# JOYPAD.net
KiCad netlist of a schematic drawn in EAGLE
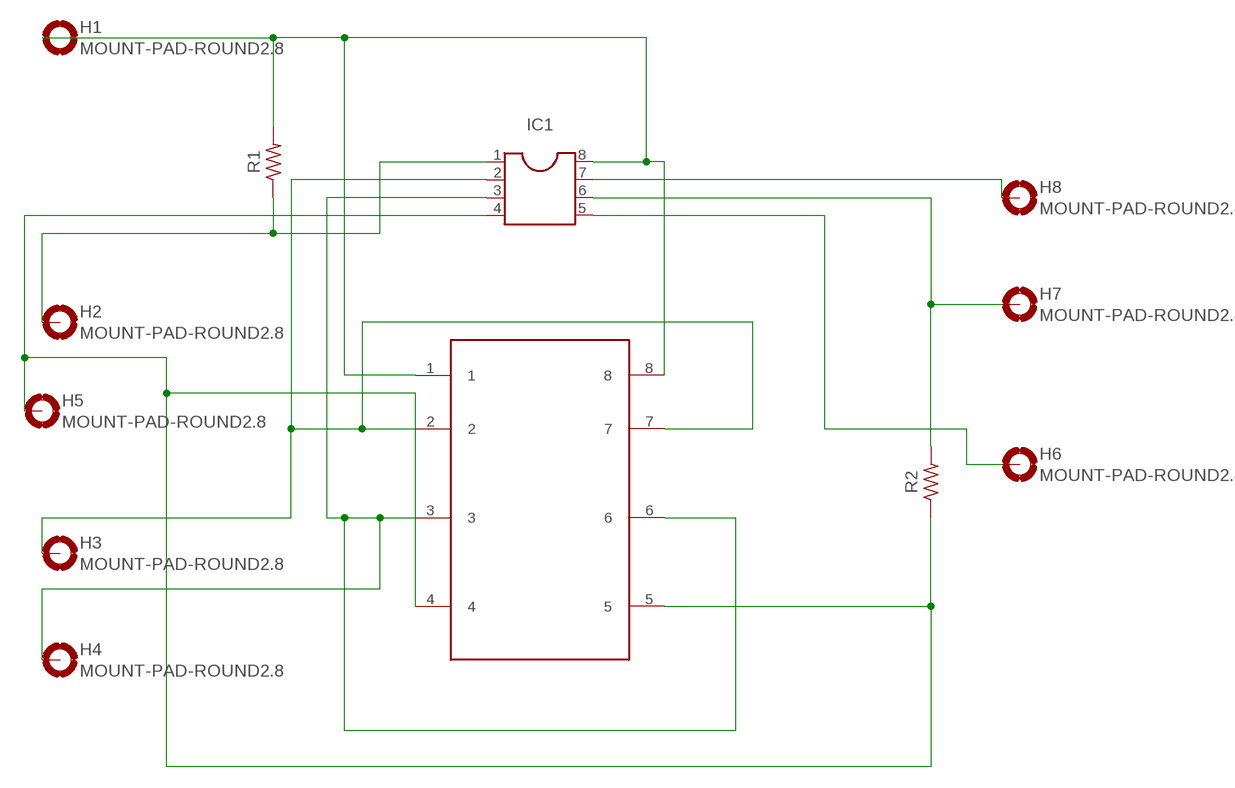
[diagram p0: schematic, sheet 1]

(export (version "E")
  (design (tool "Eeschema 10.0.6"))
  (components
    (comp (ref "H1")
      (value "MOUNT-PAD-ROUND2.8")
      (footprint "eagle-import:2,8-PAD")
      (libsource (lib "eagle-import") (part "MOUNT-PAD-ROUND2.8"))
    )
    (comp (ref "H2")
      (value "MOUNT-PAD-ROUND2.8")
      (footprint "eagle-import:2,8-PAD")
      (libsource (lib "eagle-import") (part "MOUNT-PAD-ROUND2.8"))
    )
    (comp (ref "H3")
      (value "MOUNT-PAD-ROUND2.8")
      (footprint "eagle-import:2,8-PAD")
      (libsource (lib "eagle-import") (part "MOUNT-PAD-ROUND2.8"))
    )
    (comp (ref "H4")
      (value "MOUNT-PAD-ROUND2.8")
      (footprint "eagle-import:2,8-PAD")
      (libsource (lib "eagle-import") (part "MOUNT-PAD-ROUND2.8"))
    )
    (comp (ref "H5")
      (value "MOUNT-PAD-ROUND2.8")
      (footprint "eagle-import:2,8-PAD")
      (libsource (lib "eagle-import") (part "MOUNT-PAD-ROUND2.8"))
    )
    (comp (ref "H6")
      (value "MOUNT-PAD-ROUND2.8")
      (footprint "eagle-import:2,8-PAD")
      (libsource (lib "eagle-import") (part "MOUNT-PAD-ROUND2.8"))
    )
    (comp (ref "H7")
      (value "MOUNT-PAD-ROUND2.8")
      (footprint "eagle-import:2,8-PAD")
      (libsource (lib "eagle-import") (part "MOUNT-PAD-ROUND2.8"))
    )
    (comp (ref "H8")
      (value "MOUNT-PAD-ROUND2.8")
      (footprint "eagle-import:2,8-PAD")
      (libsource (lib "eagle-import") (part "MOUNT-PAD-ROUND2.8"))
    )
    (comp (ref "IC1")
      (value "DIL8")
      (footprint "eagle-import:DIL08")
      (libsource (lib "eagle-import") (part "DIL8"))
    )
    (comp (ref "R1")
      (value "R-US_AXIAL-7.2MM-PITCH")
      (footprint "eagle-import:RESAD724W46L381D178B")
      (libsource (lib "eagle-import") (part "R-USAXIAL-7.2MM-PITCH_"))
    )
    (comp (ref "R2")
      (value "R-US_AXIAL-7.2MM-PITCH")
      (footprint "eagle-import:RESAD724W46L381D178B")
      (libsource (lib "eagle-import") (part "R-USAXIAL-7.2MM-PITCH_"))
    )
    (comp (ref "U$1")
      (value "JOYPAD")
      (footprint "eagle-import:JOYPAD")
      (libsource (lib "eagle-import") (part "JOYPAD"))
    )
  )
  (nets
    (net (code "1") (name "Net-(H1-MOUNT)") (class "Default")
      (node (ref "H1") (pin "B2,8") (pinfunction "MOUNT_B2,8") (pintype "passive"))
      (node (ref "IC1") (pin "8") (pinfunction "8_8") (pintype "passive"))
      (node (ref "R1") (pin "2") (pinfunction "2_2") (pintype "passive"))
      (node (ref "U$1") (pin "1") (pinfunction "1_1") (pintype "bidirectional"))
      (node (ref "U$1") (pin "8") (pinfunction "8_8") (pintype "bidirectional"))
    )
    (net (code "2") (name "Net-(H2-MOUNT)") (class "Default")
      (node (ref "H2") (pin "B2,8") (pinfunction "MOUNT_B2,8") (pintype "passive"))
      (node (ref "IC1") (pin "1") (pinfunction "1_1") (pintype "passive"))
      (node (ref "R1") (pin "1") (pinfunction "1_1") (pintype "passive"))
    )
    (net (code "3") (name "Net-(H3-MOUNT)") (class "Default")
      (node (ref "H3") (pin "B2,8") (pinfunction "MOUNT_B2,8") (pintype "passive"))
      (node (ref "IC1") (pin "2") (pinfunction "2_2") (pintype "passive"))
      (node (ref "U$1") (pin "2") (pinfunction "2_2") (pintype "bidirectional"))
      (node (ref "U$1") (pin "7") (pinfunction "7_7") (pintype "bidirectional"))
    )
    (net (code "4") (name "Net-(H4-MOUNT)") (class "Default")
      (node (ref "H4") (pin "B2,8") (pinfunction "MOUNT_B2,8") (pintype "passive"))
      (node (ref "IC1") (pin "3") (pinfunction "3_3") (pintype "passive"))
      (node (ref "U$1") (pin "3") (pinfunction "3_3") (pintype "bidirectional"))
      (node (ref "U$1") (pin "6") (pinfunction "6_6") (pintype "bidirectional"))
    )
    (net (code "5") (name "Net-(H5-MOUNT)") (class "Default")
      (node (ref "H5") (pin "B2,8") (pinfunction "MOUNT_B2,8") (pintype "passive"))
      (node (ref "IC1") (pin "4") (pinfunction "4_4") (pintype "passive"))
      (node (ref "R2") (pin "1") (pinfunction "1_1") (pintype "passive"))
      (node (ref "U$1") (pin "4") (pinfunction "4_4") (pintype "bidirectional"))
      (node (ref "U$1") (pin "5") (pinfunction "5_5") (pintype "bidirectional"))
    )
    (net (code "6") (name "Net-(H6-MOUNT)") (class "Default")
      (node (ref "H6") (pin "B2,8") (pinfunction "MOUNT_B2,8") (pintype "passive"))
      (node (ref "IC1") (pin "5") (pinfunction "5_5") (pintype "passive"))
    )
    (net (code "7") (name "Net-(H7-MOUNT)") (class "Default")
      (node (ref "H7") (pin "B2,8") (pinfunction "MOUNT_B2,8") (pintype "passive"))
      (node (ref "IC1") (pin "6") (pinfunction "6_6") (pintype "passive"))
      (node (ref "R2") (pin "2") (pinfunction "2_2") (pintype "passive"))
    )
    (net (code "8") (name "Net-(H8-MOUNT)") (class "Default")
      (node (ref "H8") (pin "B2,8") (pinfunction "MOUNT_B2,8") (pintype "passive"))
      (node (ref "IC1") (pin "7") (pinfunction "7_7") (pintype "passive"))
    )
  )
)
